# R220X.net
KiCad netlist of a schematic drawn in EAGLE
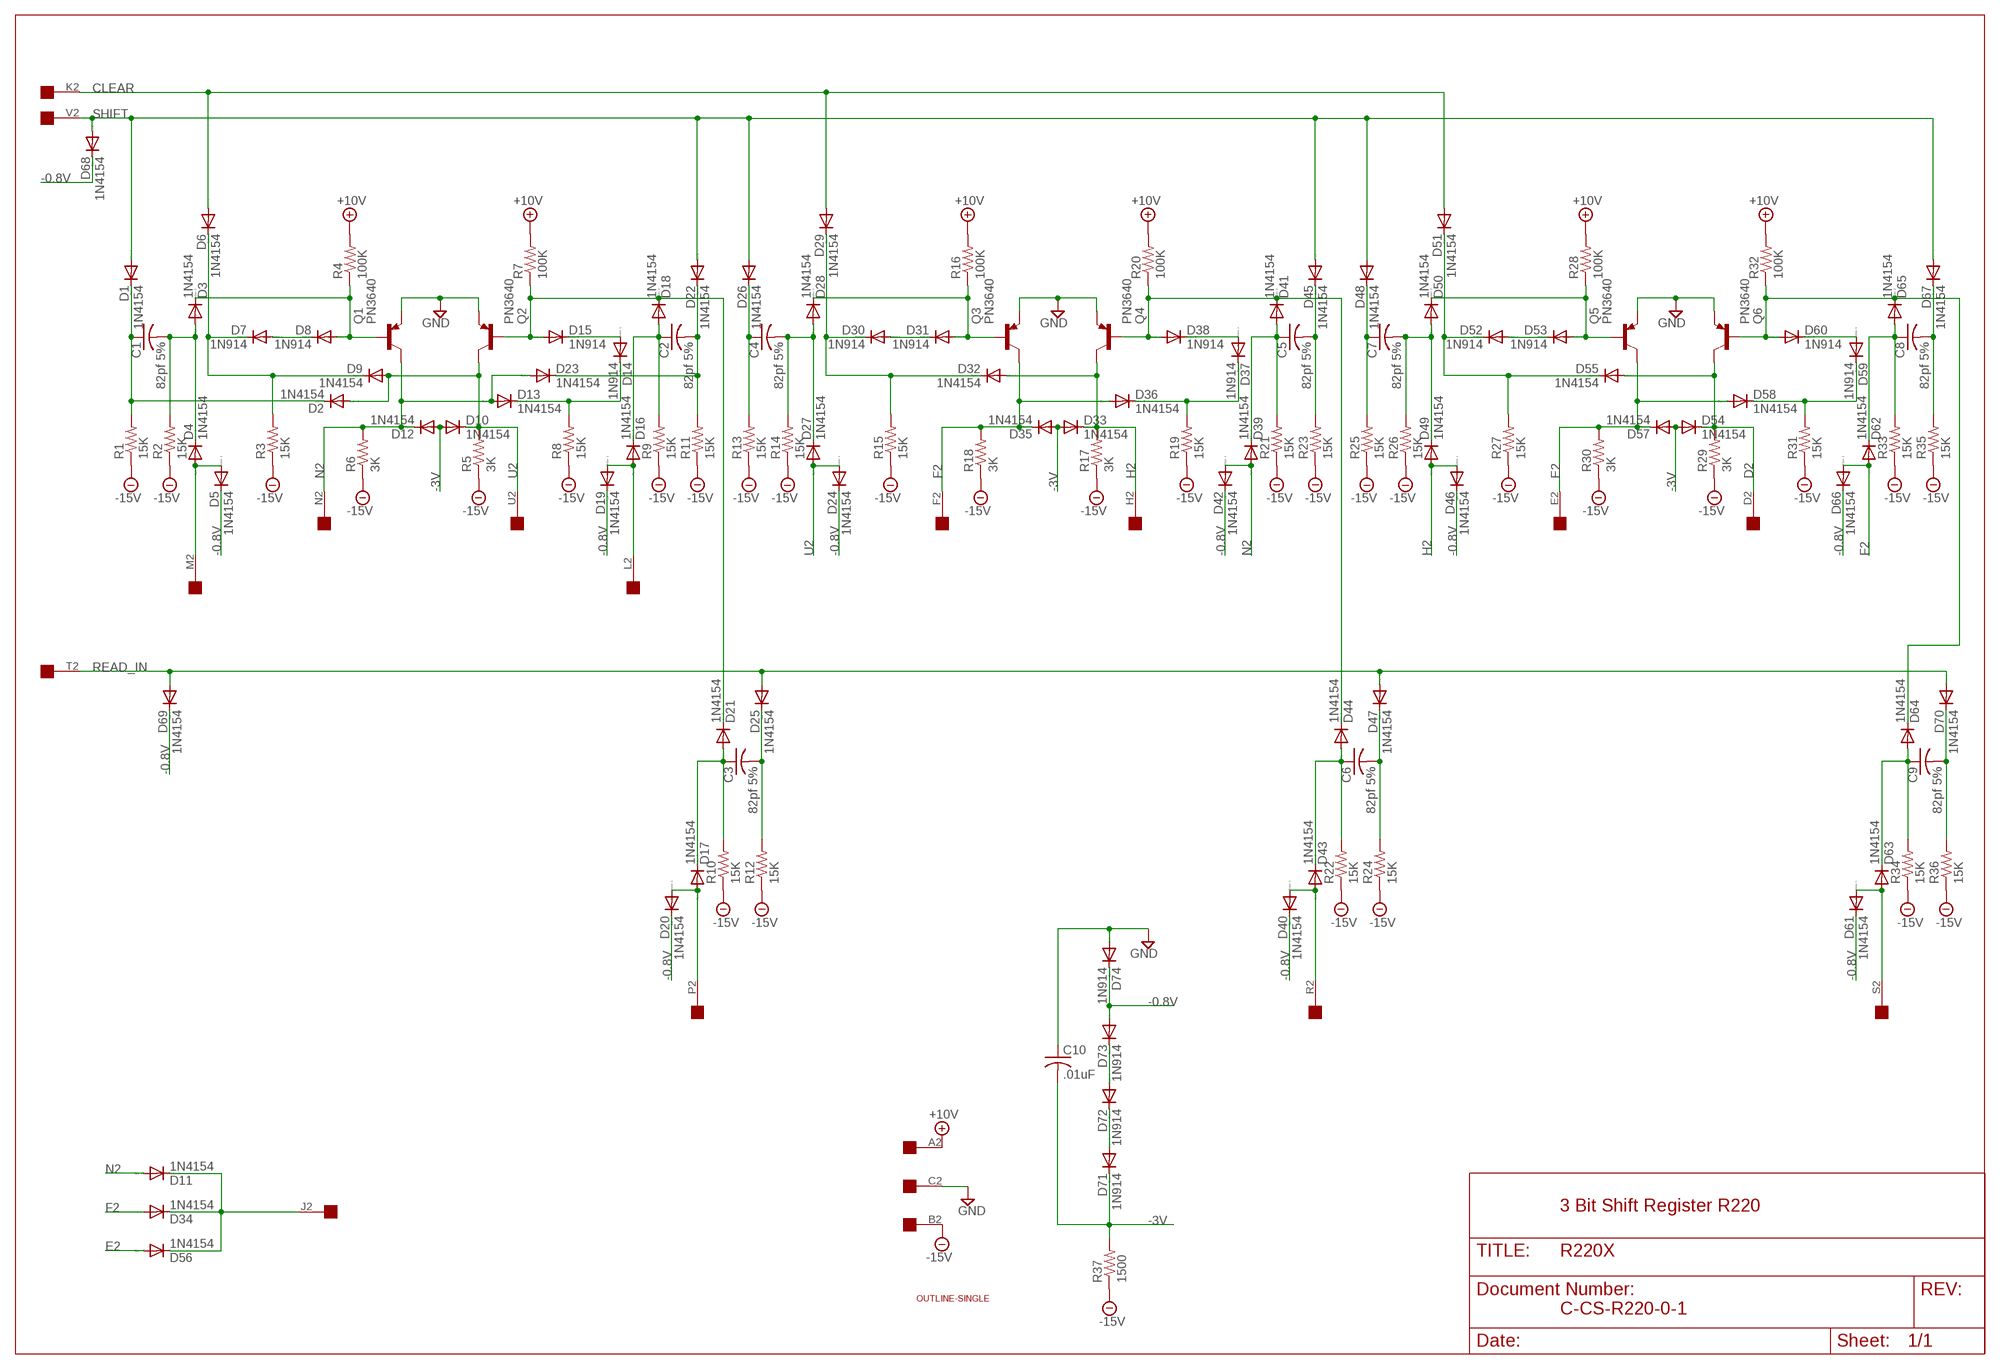
[diagram p0: schematic, sheet 1]

(export (version "E")
  (design (tool "Eeschema 10.0.6"))
  (components
    (comp (ref "C1")
      (value "82pf 5%")
      (footprint "eagle-import:C050-025X075")
      (libsource (lib "eagle-import") (part "C-US050-025X075"))
    )
    (comp (ref "C2")
      (value "82pf 5%")
      (footprint "eagle-import:C050-025X075")
      (libsource (lib "eagle-import") (part "C-US050-025X075"))
    )
    (comp (ref "C3")
      (value "82pf 5%")
      (footprint "eagle-import:C050-025X075")
      (libsource (lib "eagle-import") (part "C-US050-025X075"))
    )
    (comp (ref "C4")
      (value "82pf 5%")
      (footprint "eagle-import:C050-025X075")
      (libsource (lib "eagle-import") (part "C-US050-025X075"))
    )
    (comp (ref "C5")
      (value "82pf 5%")
      (footprint "eagle-import:C050-025X075")
      (libsource (lib "eagle-import") (part "C-US050-025X075"))
    )
    (comp (ref "C6")
      (value "82pf 5%")
      (footprint "eagle-import:C050-025X075")
      (libsource (lib "eagle-import") (part "C-US050-025X075"))
    )
    (comp (ref "C7")
      (value "82pf 5%")
      (footprint "eagle-import:C050-025X075")
      (libsource (lib "eagle-import") (part "C-US050-025X075"))
    )
    (comp (ref "C8")
      (value "82pf 5%")
      (footprint "eagle-import:C050-025X075")
      (libsource (lib "eagle-import") (part "C-US050-025X075"))
    )
    (comp (ref "C9")
      (value "82pf 5%")
      (footprint "eagle-import:C050-025X075")
      (libsource (lib "eagle-import") (part "C-US050-025X075"))
    )
    (comp (ref "C10")
      (value ".01uF")
      (footprint "eagle-import:C050-025X075")
      (libsource (lib "eagle-import") (part "C-US050-025X075"))
    )
    (comp (ref "D1")
      (value "1N4154")
      (footprint "eagle-import:DO35-10")
      (libsource (lib "eagle-import") (part "1N4148DO35-10"))
    )
    (comp (ref "D2")
      (value "1N4154")
      (footprint "eagle-import:DO35-10")
      (libsource (lib "eagle-import") (part "1N4148DO35-10"))
    )
    (comp (ref "D3")
      (value "1N4154")
      (footprint "eagle-import:DO35-10")
      (libsource (lib "eagle-import") (part "1N4148DO35-10"))
    )
    (comp (ref "D4")
      (value "1N4154")
      (footprint "eagle-import:DO35-10")
      (libsource (lib "eagle-import") (part "1N4148DO35-10"))
    )
    (comp (ref "D5")
      (value "1N4154")
      (footprint "eagle-import:DO35-10")
      (libsource (lib "eagle-import") (part "1N4148DO35-10"))
    )
    (comp (ref "D6")
      (value "1N4154")
      (footprint "eagle-import:DO35-10")
      (libsource (lib "eagle-import") (part "1N4148DO35-10"))
    )
    (comp (ref "D7")
      (value "1N914")
      (footprint "eagle-import:DO35-10")
      (libsource (lib "eagle-import") (part "1N4148DO35-10"))
    )
    (comp (ref "D8")
      (value "1N914")
      (footprint "eagle-import:DO35-10")
      (libsource (lib "eagle-import") (part "1N4148DO35-10"))
    )
    (comp (ref "D9")
      (value "1N4154")
      (footprint "eagle-import:DO35-10")
      (libsource (lib "eagle-import") (part "1N4148DO35-10"))
    )
    (comp (ref "D10")
      (value "1N4154")
      (footprint "eagle-import:DO35-10")
      (libsource (lib "eagle-import") (part "1N4148DO35-10"))
    )
    (comp (ref "D11")
      (value "1N4154")
      (footprint "eagle-import:DO35-10")
      (libsource (lib "eagle-import") (part "1N4148DO35-10"))
    )
    (comp (ref "D12")
      (value "1N4154")
      (footprint "eagle-import:DO35-10")
      (libsource (lib "eagle-import") (part "1N4148DO35-10"))
    )
    (comp (ref "D13")
      (value "1N4154")
      (footprint "eagle-import:DO35-10")
      (libsource (lib "eagle-import") (part "1N4148DO35-10"))
    )
    (comp (ref "D14")
      (value "1N914")
      (footprint "eagle-import:DO35-10")
      (libsource (lib "eagle-import") (part "1N4148DO35-10"))
    )
    (comp (ref "D15")
      (value "1N914")
      (footprint "eagle-import:DO35-10")
      (libsource (lib "eagle-import") (part "1N4148DO35-10"))
    )
    (comp (ref "D16")
      (value "1N4154")
      (footprint "eagle-import:DO35-10")
      (libsource (lib "eagle-import") (part "1N4148DO35-10"))
    )
    (comp (ref "D17")
      (value "1N4154")
      (footprint "eagle-import:DO35-10")
      (libsource (lib "eagle-import") (part "1N4148DO35-10"))
    )
    (comp (ref "D18")
      (value "1N4154")
      (footprint "eagle-import:DO35-10")
      (libsource (lib "eagle-import") (part "1N4148DO35-10"))
    )
    (comp (ref "D19")
      (value "1N4154")
      (footprint "eagle-import:DO35-10")
      (libsource (lib "eagle-import") (part "1N4148DO35-10"))
    )
    (comp (ref "D20")
      (value "1N4154")
      (footprint "eagle-import:DO35-10")
      (libsource (lib "eagle-import") (part "1N4148DO35-10"))
    )
    (comp (ref "D21")
      (value "1N4154")
      (footprint "eagle-import:DO35-10")
      (libsource (lib "eagle-import") (part "1N4148DO35-10"))
    )
    (comp (ref "D22")
      (value "1N4154")
      (footprint "eagle-import:DO35-10")
      (libsource (lib "eagle-import") (part "1N4148DO35-10"))
    )
    (comp (ref "D23")
      (value "1N4154")
      (footprint "eagle-import:DO35-10")
      (libsource (lib "eagle-import") (part "1N4148DO35-10"))
    )
    (comp (ref "D24")
      (value "1N4154")
      (footprint "eagle-import:DO35-10")
      (libsource (lib "eagle-import") (part "1N4148DO35-10"))
    )
    (comp (ref "D25")
      (value "1N4154")
      (footprint "eagle-import:DO35-10")
      (libsource (lib "eagle-import") (part "1N4148DO35-10"))
    )
    (comp (ref "D26")
      (value "1N4154")
      (footprint "eagle-import:DO35-10")
      (libsource (lib "eagle-import") (part "1N4148DO35-10"))
    )
    (comp (ref "D27")
      (value "1N4154")
      (footprint "eagle-import:DO35-10")
      (libsource (lib "eagle-import") (part "1N4148DO35-10"))
    )
    (comp (ref "D28")
      (value "1N4154")
      (footprint "eagle-import:DO35-10")
      (libsource (lib "eagle-import") (part "1N4148DO35-10"))
    )
    (comp (ref "D29")
      (value "1N4154")
      (footprint "eagle-import:DO35-10")
      (libsource (lib "eagle-import") (part "1N4148DO35-10"))
    )
    (comp (ref "D30")
      (value "1N914")
      (footprint "eagle-import:DO35-10")
      (libsource (lib "eagle-import") (part "1N4148DO35-10"))
    )
    (comp (ref "D31")
      (value "1N914")
      (footprint "eagle-import:DO35-10")
      (libsource (lib "eagle-import") (part "1N4148DO35-10"))
    )
    (comp (ref "D32")
      (value "1N4154")
      (footprint "eagle-import:DO35-10")
      (libsource (lib "eagle-import") (part "1N4148DO35-10"))
    )
    (comp (ref "D33")
      (value "1N4154")
      (footprint "eagle-import:DO35-10")
      (libsource (lib "eagle-import") (part "1N4148DO35-10"))
    )
    (comp (ref "D34")
      (value "1N4154")
      (footprint "eagle-import:DO35-10")
      (libsource (lib "eagle-import") (part "1N4148DO35-10"))
    )
    (comp (ref "D35")
      (value "1N4154")
      (footprint "eagle-import:DO35-10")
      (libsource (lib "eagle-import") (part "1N4148DO35-10"))
    )
    (comp (ref "D36")
      (value "1N4154")
      (footprint "eagle-import:DO35-10")
      (libsource (lib "eagle-import") (part "1N4148DO35-10"))
    )
    (comp (ref "D37")
      (value "1N914")
      (footprint "eagle-import:DO35-10")
      (libsource (lib "eagle-import") (part "1N4148DO35-10"))
    )
    (comp (ref "D38")
      (value "1N914")
      (footprint "eagle-import:DO35-10")
      (libsource (lib "eagle-import") (part "1N4148DO35-10"))
    )
    (comp (ref "D39")
      (value "1N4154")
      (footprint "eagle-import:DO35-10")
      (libsource (lib "eagle-import") (part "1N4148DO35-10"))
    )
    (comp (ref "D40")
      (value "1N4154")
      (footprint "eagle-import:DO35-10")
      (libsource (lib "eagle-import") (part "1N4148DO35-10"))
    )
    (comp (ref "D41")
      (value "1N4154")
      (footprint "eagle-import:DO35-10")
      (libsource (lib "eagle-import") (part "1N4148DO35-10"))
    )
    (comp (ref "D42")
      (value "1N4154")
      (footprint "eagle-import:DO35-10")
      (libsource (lib "eagle-import") (part "1N4148DO35-10"))
    )
    (comp (ref "D43")
      (value "1N4154")
      (footprint "eagle-import:DO35-10")
      (libsource (lib "eagle-import") (part "1N4148DO35-10"))
    )
    (comp (ref "D44")
      (value "1N4154")
      (footprint "eagle-import:DO35-10")
      (libsource (lib "eagle-import") (part "1N4148DO35-10"))
    )
    (comp (ref "D45")
      (value "1N4154")
      (footprint "eagle-import:DO35-10")
      (libsource (lib "eagle-import") (part "1N4148DO35-10"))
    )
    (comp (ref "D46")
      (value "1N4154")
      (footprint "eagle-import:DO35-10")
      (libsource (lib "eagle-import") (part "1N4148DO35-10"))
    )
    (comp (ref "D47")
      (value "1N4154")
      (footprint "eagle-import:DO35-10")
      (libsource (lib "eagle-import") (part "1N4148DO35-10"))
    )
    (comp (ref "D48")
      (value "1N4154")
      (footprint "eagle-import:DO35-10")
      (libsource (lib "eagle-import") (part "1N4148DO35-10"))
    )
    (comp (ref "D49")
      (value "1N4154")
      (footprint "eagle-import:DO35-10")
      (libsource (lib "eagle-import") (part "1N4148DO35-10"))
    )
    (comp (ref "D50")
      (value "1N4154")
      (footprint "eagle-import:DO35-10")
      (libsource (lib "eagle-import") (part "1N4148DO35-10"))
    )
    (comp (ref "D51")
      (value "1N4154")
      (footprint "eagle-import:DO35-10")
      (libsource (lib "eagle-import") (part "1N4148DO35-10"))
    )
    (comp (ref "D52")
      (value "1N914")
      (footprint "eagle-import:DO35-10")
      (libsource (lib "eagle-import") (part "1N4148DO35-10"))
    )
    (comp (ref "D53")
      (value "1N914")
      (footprint "eagle-import:DO35-10")
      (libsource (lib "eagle-import") (part "1N4148DO35-10"))
    )
    (comp (ref "D54")
      (value "1N4154")
      (footprint "eagle-import:DO35-10")
      (libsource (lib "eagle-import") (part "1N4148DO35-10"))
    )
    (comp (ref "D55")
      (value "1N4154")
      (footprint "eagle-import:DO35-10")
      (libsource (lib "eagle-import") (part "1N4148DO35-10"))
    )
    (comp (ref "D56")
      (value "1N4154")
      (footprint "eagle-import:DO35-10")
      (libsource (lib "eagle-import") (part "1N4148DO35-10"))
    )
    (comp (ref "D57")
      (value "1N4154")
      (footprint "eagle-import:DO35-10")
      (libsource (lib "eagle-import") (part "1N4148DO35-10"))
    )
    (comp (ref "D58")
      (value "1N4154")
      (footprint "eagle-import:DO35-10")
      (libsource (lib "eagle-import") (part "1N4148DO35-10"))
    )
    (comp (ref "D59")
      (value "1N914")
      (footprint "eagle-import:DO35-10")
      (libsource (lib "eagle-import") (part "1N4148DO35-10"))
    )
    (comp (ref "D60")
      (value "1N914")
      (footprint "eagle-import:DO35-10")
      (libsource (lib "eagle-import") (part "1N4148DO35-10"))
    )
    (comp (ref "D61")
      (value "1N4154")
      (footprint "eagle-import:DO35-10")
      (libsource (lib "eagle-import") (part "1N4148DO35-10"))
    )
    (comp (ref "D62")
      (value "1N4154")
      (footprint "eagle-import:DO35-10")
      (libsource (lib "eagle-import") (part "1N4148DO35-10"))
    )
    (comp (ref "D63")
      (value "1N4154")
      (footprint "eagle-import:DO35-10")
      (libsource (lib "eagle-import") (part "1N4148DO35-10"))
    )
    (comp (ref "D64")
      (value "1N4154")
      (footprint "eagle-import:DO35-10")
      (libsource (lib "eagle-import") (part "1N4148DO35-10"))
    )
    (comp (ref "D65")
      (value "1N4154")
      (footprint "eagle-import:DO35-10")
      (libsource (lib "eagle-import") (part "1N4148DO35-10"))
    )
    (comp (ref "D66")
      (value "1N4154")
      (footprint "eagle-import:DO35-10")
      (libsource (lib "eagle-import") (part "1N4148DO35-10"))
    )
    (comp (ref "D67")
      (value "1N4154")
      (footprint "eagle-import:DO35-10")
      (libsource (lib "eagle-import") (part "1N4148DO35-10"))
    )
    (comp (ref "D68")
      (value "1N4154")
      (footprint "eagle-import:DO35-10")
      (libsource (lib "eagle-import") (part "1N4148DO35-10"))
    )
    (comp (ref "D69")
      (value "1N4154")
      (footprint "eagle-import:DO35-10")
      (libsource (lib "eagle-import") (part "1N4148DO35-10"))
    )
    (comp (ref "D70")
      (value "1N4154")
      (footprint "eagle-import:DO35-10")
      (libsource (lib "eagle-import") (part "1N4148DO35-10"))
    )
    (comp (ref "D71")
      (value "1N914")
      (footprint "eagle-import:DO35-10")
      (libsource (lib "eagle-import") (part "1N4148DO35-10"))
    )
    (comp (ref "D72")
      (value "1N914")
      (footprint "eagle-import:DO35-10")
      (libsource (lib "eagle-import") (part "1N4148DO35-10"))
    )
    (comp (ref "D73")
      (value "1N914")
      (footprint "eagle-import:DO35-10")
      (libsource (lib "eagle-import") (part "1N4148DO35-10"))
    )
    (comp (ref "D74")
      (value "1N914")
      (footprint "eagle-import:DO35-10")
      (libsource (lib "eagle-import") (part "1N4148DO35-10"))
    )
    (comp (ref "Q1")
      (value "PN3640")
      (footprint "eagle-import:TO39")
      (libsource (lib "eagle-import") (part "2N3637"))
    )
    (comp (ref "Q2")
      (value "PN3640")
      (footprint "eagle-import:TO39")
      (libsource (lib "eagle-import") (part "2N3637"))
    )
    (comp (ref "Q3")
      (value "PN3640")
      (footprint "eagle-import:TO39")
      (libsource (lib "eagle-import") (part "2N3637"))
    )
    (comp (ref "Q4")
      (value "PN3640")
      (footprint "eagle-import:TO39")
      (libsource (lib "eagle-import") (part "2N3637"))
    )
    (comp (ref "Q5")
      (value "PN3640")
      (footprint "eagle-import:TO39")
      (libsource (lib "eagle-import") (part "2N3637"))
    )
    (comp (ref "Q6")
      (value "PN3640")
      (footprint "eagle-import:TO39")
      (libsource (lib "eagle-import") (part "2N3637"))
    )
    (comp (ref "R1")
      (value "15K")
      (footprint "eagle-import:0207_10")
      (libsource (lib "eagle-import") (part "R-US_0207/10"))
    )
    (comp (ref "R2")
      (value "15K")
      (footprint "eagle-import:0207_10")
      (libsource (lib "eagle-import") (part "R-US_0207/10"))
    )
    (comp (ref "R3")
      (value "15K")
      (footprint "eagle-import:0207_10")
      (libsource (lib "eagle-import") (part "R-US_0207/10"))
    )
    (comp (ref "R4")
      (value "100K")
      (footprint "eagle-import:0207_10")
      (libsource (lib "eagle-import") (part "R-US_0207/10"))
    )
    (comp (ref "R5")
      (value "3K")
      (footprint "eagle-import:0207_10")
      (libsource (lib "eagle-import") (part "R-US_0207/10"))
    )
    (comp (ref "R6")
      (value "3K")
      (footprint "eagle-import:0207_10")
      (libsource (lib "eagle-import") (part "R-US_0207/10"))
    )
    (comp (ref "R7")
      (value "100K")
      (footprint "eagle-import:0207_10")
      (libsource (lib "eagle-import") (part "R-US_0207/10"))
    )
    (comp (ref "R8")
      (value "15K")
      (footprint "eagle-import:0207_10")
      (libsource (lib "eagle-import") (part "R-US_0207/10"))
    )
    (comp (ref "R9")
      (value "15K")
      (footprint "eagle-import:0207_10")
      (libsource (lib "eagle-import") (part "R-US_0207/10"))
    )
    (comp (ref "R10")
      (value "15K")
      (footprint "eagle-import:0207_10")
      (libsource (lib "eagle-import") (part "R-US_0207/10"))
    )
    (comp (ref "R11")
      (value "15K")
      (footprint "eagle-import:0207_10")
      (libsource (lib "eagle-import") (part "R-US_0207/10"))
    )
    (comp (ref "R12")
      (value "15K")
      (footprint "eagle-import:0207_10")
      (libsource (lib "eagle-import") (part "R-US_0207/10"))
    )
    (comp (ref "R13")
      (value "15K")
      (footprint "eagle-import:0207_10")
      (libsource (lib "eagle-import") (part "R-US_0207/10"))
    )
    (comp (ref "R14")
      (value "15K")
      (footprint "eagle-import:0207_10")
      (libsource (lib "eagle-import") (part "R-US_0207/10"))
    )
    (comp (ref "R15")
      (value "15K")
      (footprint "eagle-import:0207_10")
      (libsource (lib "eagle-import") (part "R-US_0207/10"))
    )
    (comp (ref "R16")
      (value "100K")
      (footprint "eagle-import:0207_10")
      (libsource (lib "eagle-import") (part "R-US_0207/10"))
    )
    (comp (ref "R17")
      (value "3K")
      (footprint "eagle-import:0207_10")
      (libsource (lib "eagle-import") (part "R-US_0207/10"))
    )
    (comp (ref "R18")
      (value "3K")
      (footprint "eagle-import:0207_10")
      (libsource (lib "eagle-import") (part "R-US_0207/10"))
    )
    (comp (ref "R19")
      (value "15K")
      (footprint "eagle-import:0207_10")
      (libsource (lib "eagle-import") (part "R-US_0207/10"))
    )
    (comp (ref "R20")
      (value "100K")
      (footprint "eagle-import:0207_10")
      (libsource (lib "eagle-import") (part "R-US_0207/10"))
    )
    (comp (ref "R21")
      (value "15K")
      (footprint "eagle-import:0207_10")
      (libsource (lib "eagle-import") (part "R-US_0207/10"))
    )
    (comp (ref "R22")
      (value "15K")
      (footprint "eagle-import:0207_10")
      (libsource (lib "eagle-import") (part "R-US_0207/10"))
    )
    (comp (ref "R23")
      (value "15K")
      (footprint "eagle-import:0207_10")
      (libsource (lib "eagle-import") (part "R-US_0207/10"))
    )
    (comp (ref "R24")
      (value "15K")
      (footprint "eagle-import:0207_10")
      (libsource (lib "eagle-import") (part "R-US_0207/10"))
    )
    (comp (ref "R25")
      (value "15K")
      (footprint "eagle-import:0207_10")
      (libsource (lib "eagle-import") (part "R-US_0207/10"))
    )
    (comp (ref "R26")
      (value "15K")
      (footprint "eagle-import:0207_10")
      (libsource (lib "eagle-import") (part "R-US_0207/10"))
    )
    (comp (ref "R27")
      (value "15K")
      (footprint "eagle-import:0207_10")
      (libsource (lib "eagle-import") (part "R-US_0207/10"))
    )
    (comp (ref "R28")
      (value "100K")
      (footprint "eagle-import:0207_10")
      (libsource (lib "eagle-import") (part "R-US_0207/10"))
    )
    (comp (ref "R29")
      (value "3K")
      (footprint "eagle-import:0207_10")
      (libsource (lib "eagle-import") (part "R-US_0207/10"))
    )
    (comp (ref "R30")
      (value "3K")
      (footprint "eagle-import:0207_10")
      (libsource (lib "eagle-import") (part "R-US_0207/10"))
    )
    (comp (ref "R31")
      (value "15K")
      (footprint "eagle-import:0207_10")
      (libsource (lib "eagle-import") (part "R-US_0207/10"))
    )
    (comp (ref "R32")
      (value "100K")
      (footprint "eagle-import:0207_10")
      (libsource (lib "eagle-import") (part "R-US_0207/10"))
    )
    (comp (ref "R33")
      (value "15K")
      (footprint "eagle-import:0207_10")
      (libsource (lib "eagle-import") (part "R-US_0207/10"))
    )
    (comp (ref "R34")
      (value "15K")
      (footprint "eagle-import:0207_10")
      (libsource (lib "eagle-import") (part "R-US_0207/10"))
    )
    (comp (ref "R35")
      (value "15K")
      (footprint "eagle-import:0207_10")
      (libsource (lib "eagle-import") (part "R-US_0207/10"))
    )
    (comp (ref "R36")
      (value "15K")
      (footprint "eagle-import:0207_10")
      (libsource (lib "eagle-import") (part "R-US_0207/10"))
    )
    (comp (ref "R37")
      (value "1500")
      (footprint "eagle-import:0207_10")
      (libsource (lib "eagle-import") (part "R-US_0207/10"))
    )
    (comp (ref "U$1")
      (value "OUTLINE-SINGLE")
      (footprint "eagle-import:SINGLE")
      (libsource (lib "eagle-import") (part "OUTLINE-SINGLE"))
    )
    (comp (ref "U$2")
      (value "EDGE-1")
      (footprint "eagle-import:EDGE-CON1")
      (libsource (lib "eagle-import") (part "EDGE-1"))
    )
  )
  (nets
    (net (code "1") (name "+10V") (class "Default")
      (node (ref "R16") (pin "2") (pinfunction "2_2") (pintype "passive"))
      (node (ref "R20") (pin "2") (pinfunction "2_2") (pintype "passive"))
      (node (ref "R28") (pin "2") (pinfunction "2_2") (pintype "passive"))
      (node (ref "R32") (pin "2") (pinfunction "2_2") (pintype "passive"))
      (node (ref "R4") (pin "2") (pinfunction "2_2") (pintype "passive"))
      (node (ref "R7") (pin "2") (pinfunction "2_2") (pintype "passive"))
      (node (ref "U$2") (pin "A2") (pinfunction "1_A2") (pintype "bidirectional"))
    )
    (net (code "2") (name "-15V") (class "Default")
      (node (ref "R1") (pin "1") (pinfunction "1_1") (pintype "passive"))
      (node (ref "R10") (pin "1") (pinfunction "1_1") (pintype "passive"))
      (node (ref "R11") (pin "1") (pinfunction "1_1") (pintype "passive"))
      (node (ref "R12") (pin "1") (pinfunction "1_1") (pintype "passive"))
      (node (ref "R13") (pin "1") (pinfunction "1_1") (pintype "passive"))
      (node (ref "R14") (pin "1") (pinfunction "1_1") (pintype "passive"))
      (node (ref "R15") (pin "1") (pinfunction "1_1") (pintype "passive"))
      (node (ref "R17") (pin "1") (pinfunction "1_1") (pintype "passive"))
      (node (ref "R18") (pin "1") (pinfunction "1_1") (pintype "passive"))
      (node (ref "R19") (pin "1") (pinfunction "1_1") (pintype "passive"))
      (node (ref "R2") (pin "1") (pinfunction "1_1") (pintype "passive"))
      (node (ref "R21") (pin "1") (pinfunction "1_1") (pintype "passive"))
      (node (ref "R22") (pin "1") (pinfunction "1_1") (pintype "passive"))
      (node (ref "R23") (pin "1") (pinfunction "1_1") (pintype "passive"))
      (node (ref "R24") (pin "1") (pinfunction "1_1") (pintype "passive"))
      (node (ref "R25") (pin "1") (pinfunction "1_1") (pintype "passive"))
      (node (ref "R26") (pin "1") (pinfunction "1_1") (pintype "passive"))
      (node (ref "R27") (pin "1") (pinfunction "1_1") (pintype "passive"))
      (node (ref "R29") (pin "1") (pinfunction "1_1") (pintype "passive"))
      (node (ref "R3") (pin "1") (pinfunction "1_1") (pintype "passive"))
      (node (ref "R30") (pin "1") (pinfunction "1_1") (pintype "passive"))
      (node (ref "R31") (pin "1") (pinfunction "1_1") (pintype "passive"))
      (node (ref "R33") (pin "1") (pinfunction "1_1") (pintype "passive"))
      (node (ref "R34") (pin "1") (pinfunction "1_1") (pintype "passive"))
      (node (ref "R35") (pin "1") (pinfunction "1_1") (pintype "passive"))
      (node (ref "R36") (pin "1") (pinfunction "1_1") (pintype "passive"))
      (node (ref "R37") (pin "1") (pinfunction "1_1") (pintype "passive"))
      (node (ref "R5") (pin "1") (pinfunction "1_1") (pintype "passive"))
      (node (ref "R6") (pin "1") (pinfunction "1_1") (pintype "passive"))
      (node (ref "R8") (pin "1") (pinfunction "1_1") (pintype "passive"))
      (node (ref "R9") (pin "1") (pinfunction "1_1") (pintype "passive"))
      (node (ref "U$2") (pin "B2") (pinfunction "1_B2") (pintype "bidirectional"))
    )
    (net (code "3") (name "/-0.8V") (class "Default")
      (node (ref "D19") (pin "C") (pinfunction "C_C") (pintype "passive"))
      (node (ref "D20") (pin "C") (pinfunction "C_C") (pintype "passive"))
      (node (ref "D24") (pin "C") (pinfunction "C_C") (pintype "passive"))
      (node (ref "D40") (pin "C") (pinfunction "C_C") (pintype "passive"))
      (node (ref "D42") (pin "C") (pinfunction "C_C") (pintype "passive"))
      (node (ref "D46") (pin "C") (pinfunction "C_C") (pintype "passive"))
      (node (ref "D5") (pin "C") (pinfunction "C_C") (pintype "passive"))
      (node (ref "D61") (pin "C") (pinfunction "C_C") (pintype "passive"))
      (node (ref "D66") (pin "C") (pinfunction "C_C") (pintype "passive"))
      (node (ref "D68") (pin "C") (pinfunction "C_C") (pintype "passive"))
      (node (ref "D69") (pin "C") (pinfunction "C_C") (pintype "passive"))
      (node (ref "D73") (pin "A") (pinfunction "A_A") (pintype "passive"))
      (node (ref "D74") (pin "C") (pinfunction "C_C") (pintype "passive"))
    )
    (net (code "4") (name "/-3V") (class "Default")
      (node (ref "C10") (pin "2") (pinfunction "2_2") (pintype "passive"))
      (node (ref "D10") (pin "A") (pinfunction "A_A") (pintype "passive"))
      (node (ref "D12") (pin "A") (pinfunction "A_A") (pintype "passive"))
      (node (ref "D33") (pin "A") (pinfunction "A_A") (pintype "passive"))
      (node (ref "D35") (pin "A") (pinfunction "A_A") (pintype "passive"))
      (node (ref "D54") (pin "A") (pinfunction "A_A") (pintype "passive"))
      (node (ref "D57") (pin "A") (pinfunction "A_A") (pintype "passive"))
      (node (ref "D71") (pin "C") (pinfunction "C_C") (pintype "passive"))
      (node (ref "R37") (pin "2") (pinfunction "2_2") (pintype "passive"))
    )
    (net (code "5") (name "/CLEAR") (class "Default")
      (node (ref "D29") (pin "A") (pinfunction "A_A") (pintype "passive"))
      (node (ref "D51") (pin "A") (pinfunction "A_A") (pintype "passive"))
      (node (ref "D6") (pin "A") (pinfunction "A_A") (pintype "passive"))
      (node (ref "U$2") (pin "K2") (pinfunction "1_K2") (pintype "bidirectional"))
    )
    (net (code "6") (name "/D2") (class "Default")
      (node (ref "D54") (pin "C") (pinfunction "C_C") (pintype "passive"))
      (node (ref "D55") (pin "A") (pinfunction "A_A") (pintype "passive"))
      (node (ref "Q6") (pin "3") (pinfunction "C_3") (pintype "passive"))
      (node (ref "R29") (pin "2") (pinfunction "2_2") (pintype "passive"))
      (node (ref "U$2") (pin "D2") (pinfunction "1_D2") (pintype "bidirectional"))
    )
    (net (code "7") (name "/E2") (class "Default")
      (node (ref "D56") (pin "A") (pinfunction "A_A") (pintype "passive"))
      (node (ref "D57") (pin "C") (pinfunction "C_C") (pintype "passive"))
      (node (ref "D58") (pin "A") (pinfunction "A_A") (pintype "passive"))
      (node (ref "Q5") (pin "3") (pinfunction "C_3") (pintype "passive"))
      (node (ref "R30") (pin "2") (pinfunction "2_2") (pintype "passive"))
      (node (ref "U$2") (pin "E2") (pinfunction "1_E2") (pintype "bidirectional"))
    )
    (net (code "8") (name "/F2") (class "Default")
      (node (ref "D34") (pin "A") (pinfunction "A_A") (pintype "passive"))
      (node (ref "D35") (pin "C") (pinfunction "C_C") (pintype "passive"))
      (node (ref "D36") (pin "A") (pinfunction "A_A") (pintype "passive"))
      (node (ref "D62") (pin "A") (pinfunction "A_A") (pintype "passive"))
      (node (ref "D66") (pin "A") (pinfunction "A_A") (pintype "passive"))
      (node (ref "Q3") (pin "3") (pinfunction "C_3") (pintype "passive"))
      (node (ref "R18") (pin "2") (pinfunction "2_2") (pintype "passive"))
      (node (ref "U$2") (pin "F2") (pinfunction "1_F2") (pintype "bidirectional"))
    )
    (net (code "9") (name "/H2") (class "Default")
      (node (ref "D32") (pin "A") (pinfunction "A_A") (pintype "passive"))
      (node (ref "D33") (pin "C") (pinfunction "C_C") (pintype "passive"))
      (node (ref "D46") (pin "A") (pinfunction "A_A") (pintype "passive"))
      (node (ref "D49") (pin "A") (pinfunction "A_A") (pintype "passive"))
      (node (ref "Q4") (pin "3") (pinfunction "C_3") (pintype "passive"))
      (node (ref "R17") (pin "2") (pinfunction "2_2") (pintype "passive"))
      (node (ref "U$2") (pin "H2") (pinfunction "1_H2") (pintype "bidirectional"))
    )
    (net (code "10") (name "/N2") (class "Default")
      (node (ref "D11") (pin "A") (pinfunction "A_A") (pintype "passive"))
      (node (ref "D12") (pin "C") (pinfunction "C_C") (pintype "passive"))
      (node (ref "D13") (pin "A") (pinfunction "A_A") (pintype "passive"))
      (node (ref "D23") (pin "A") (pinfunction "A_A") (pintype "passive"))
      (node (ref "D39") (pin "A") (pinfunction "A_A") (pintype "passive"))
      (node (ref "D42") (pin "A") (pinfunction "A_A") (pintype "passive"))
      (node (ref "Q1") (pin "3") (pinfunction "C_3") (pintype "passive"))
      (node (ref "R6") (pin "2") (pinfunction "2_2") (pintype "passive"))
      (node (ref "U$2") (pin "N2") (pinfunction "1_N2") (pintype "bidirectional"))
    )
    (net (code "11") (name "/READ_IN") (class "Default")
      (node (ref "D25") (pin "A") (pinfunction "A_A") (pintype "passive"))
      (node (ref "D47") (pin "A") (pinfunction "A_A") (pintype "passive"))
      (node (ref "D69") (pin "A") (pinfunction "A_A") (pintype "passive"))
      (node (ref "D70") (pin "A") (pinfunction "A_A") (pintype "passive"))
      (node (ref "U$2") (pin "T2") (pinfunction "1_T2") (pintype "bidirectional"))
    )
    (net (code "12") (name "/SHIFT") (class "Default")
      (node (ref "D1") (pin "A") (pinfunction "A_A") (pintype "passive"))
      (node (ref "D22") (pin "A") (pinfunction "A_A") (pintype "passive"))
      (node (ref "D26") (pin "A") (pinfunction "A_A") (pintype "passive"))
      (node (ref "D45") (pin "A") (pinfunction "A_A") (pintype "passive"))
      (node (ref "D48") (pin "A") (pinfunction "A_A") (pintype "passive"))
      (node (ref "D67") (pin "A") (pinfunction "A_A") (pintype "passive"))
      (node (ref "D68") (pin "A") (pinfunction "A_A") (pintype "passive"))
      (node (ref "U$2") (pin "V2") (pinfunction "1_V2") (pintype "bidirectional"))
    )
    (net (code "13") (name "/U2") (class "Default")
      (node (ref "D10") (pin "C") (pinfunction "C_C") (pintype "passive"))
      (node (ref "D2") (pin "A") (pinfunction "A_A") (pintype "passive"))
      (node (ref "D24") (pin "A") (pinfunction "A_A") (pintype "passive"))
      (node (ref "D27") (pin "A") (pinfunction "A_A") (pintype "passive"))
      (node (ref "D9") (pin "A") (pinfunction "A_A") (pintype "passive"))
      (node (ref "Q2") (pin "3") (pinfunction "C_3") (pintype "passive"))
      (node (ref "R5") (pin "2") (pinfunction "2_2") (pintype "passive"))
      (node (ref "U$2") (pin "U2") (pinfunction "1_U2") (pintype "bidirectional"))
    )
    (net (code "14") (name "GND") (class "Default")
      (node (ref "C10") (pin "1") (pinfunction "1_1") (pintype "passive"))
      (node (ref "D74") (pin "A") (pinfunction "A_A") (pintype "passive"))
      (node (ref "Q1") (pin "1") (pinfunction "E_1") (pintype "passive"))
      (node (ref "Q2") (pin "1") (pinfunction "E_1") (pintype "passive"))
      (node (ref "Q3") (pin "1") (pinfunction "E_1") (pintype "passive"))
      (node (ref "Q4") (pin "1") (pinfunction "E_1") (pintype "passive"))
      (node (ref "Q5") (pin "1") (pinfunction "E_1") (pintype "passive"))
      (node (ref "Q6") (pin "1") (pinfunction "E_1") (pintype "passive"))
      (node (ref "U$2") (pin "C2") (pinfunction "1_C2") (pintype "bidirectional"))
    )
    (net (code "15") (name "Net-(C1-Pad1)") (class "Default")
      (node (ref "C1") (pin "1") (pinfunction "1_1") (pintype "passive"))
      (node (ref "D1") (pin "C") (pinfunction "C_C") (pintype "passive"))
      (node (ref "D2") (pin "C") (pinfunction "C_C") (pintype "passive"))
      (node (ref "R1") (pin "2") (pinfunction "2_2") (pintype "passive"))
    )
    (net (code "16") (name "Net-(C1-Pad2)") (class "Default")
      (node (ref "C1") (pin "2") (pinfunction "2_2") (pintype "passive"))
      (node (ref "D3") (pin "A") (pinfunction "A_A") (pintype "passive"))
      (node (ref "D4") (pin "C") (pinfunction "C_C") (pintype "passive"))
      (node (ref "R2") (pin "2") (pinfunction "2_2") (pintype "passive"))
    )
    (net (code "17") (name "Net-(C2-Pad1)") (class "Default")
      (node (ref "C2") (pin "1") (pinfunction "1_1") (pintype "passive"))
      (node (ref "D16") (pin "C") (pinfunction "C_C") (pintype "passive"))
      (node (ref "D18") (pin "A") (pinfunction "A_A") (pintype "passive"))
      (node (ref "R9") (pin "2") (pinfunction "2_2") (pintype "passive"))
    )
    (net (code "18") (name "Net-(C2-Pad2)") (class "Default")
      (node (ref "C2") (pin "2") (pinfunction "2_2") (pintype "passive"))
      (node (ref "D22") (pin "C") (pinfunction "C_C") (pintype "passive"))
      (node (ref "D23") (pin "C") (pinfunction "C_C") (pintype "passive"))
      (node (ref "R11") (pin "2") (pinfunction "2_2") (pintype "passive"))
    )
    (net (code "19") (name "Net-(C3-Pad1)") (class "Default")
      (node (ref "C3") (pin "1") (pinfunction "1_1") (pintype "passive"))
      (node (ref "D17") (pin "C") (pinfunction "C_C") (pintype "passive"))
      (node (ref "D21") (pin "A") (pinfunction "A_A") (pintype "passive"))
      (node (ref "R10") (pin "2") (pinfunction "2_2") (pintype "passive"))
    )
    (net (code "20") (name "Net-(C3-Pad2)") (class "Default")
      (node (ref "C3") (pin "2") (pinfunction "2_2") (pintype "passive"))
      (node (ref "D25") (pin "C") (pinfunction "C_C") (pintype "passive"))
      (node (ref "R12") (pin "2") (pinfunction "2_2") (pintype "passive"))
    )
    (net (code "21") (name "Net-(C4-Pad1)") (class "Default")
      (node (ref "C4") (pin "1") (pinfunction "1_1") (pintype "passive"))
      (node (ref "D26") (pin "C") (pinfunction "C_C") (pintype "passive"))
      (node (ref "R13") (pin "2") (pinfunction "2_2") (pintype "passive"))
    )
    (net (code "22") (name "Net-(C4-Pad2)") (class "Default")
      (node (ref "C4") (pin "2") (pinfunction "2_2") (pintype "passive"))
      (node (ref "D27") (pin "C") (pinfunction "C_C") (pintype "passive"))
      (node (ref "D28") (pin "A") (pinfunction "A_A") (pintype "passive"))
      (node (ref "R14") (pin "2") (pinfunction "2_2") (pintype "passive"))
    )
    (net (code "23") (name "Net-(C5-Pad1)") (class "Default")
      (node (ref "C5") (pin "1") (pinfunction "1_1") (pintype "passive"))
      (node (ref "D39") (pin "C") (pinfunction "C_C") (pintype "passive"))
      (node (ref "D41") (pin "A") (pinfunction "A_A") (pintype "passive"))
      (node (ref "R21") (pin "2") (pinfunction "2_2") (pintype "passive"))
    )
    (net (code "24") (name "Net-(C5-Pad2)") (class "Default")
      (node (ref "C5") (pin "2") (pinfunction "2_2") (pintype "passive"))
      (node (ref "D45") (pin "C") (pinfunction "C_C") (pintype "passive"))
      (node (ref "R23") (pin "2") (pinfunction "2_2") (pintype "passive"))
    )
    (net (code "25") (name "Net-(C6-Pad1)") (class "Default")
      (node (ref "C6") (pin "1") (pinfunction "1_1") (pintype "passive"))
      (node (ref "D43") (pin "C") (pinfunction "C_C") (pintype "passive"))
      (node (ref "D44") (pin "A") (pinfunction "A_A") (pintype "passive"))
      (node (ref "R22") (pin "2") (pinfunction "2_2") (pintype "passive"))
    )
    (net (code "26") (name "Net-(C6-Pad2)") (class "Default")
      (node (ref "C6") (pin "2") (pinfunction "2_2") (pintype "passive"))
      (node (ref "D47") (pin "C") (pinfunction "C_C") (pintype "passive"))
      (node (ref "R24") (pin "2") (pinfunction "2_2") (pintype "passive"))
    )
    (net (code "27") (name "Net-(C7-Pad1)") (class "Default")
      (node (ref "C7") (pin "1") (pinfunction "1_1") (pintype "passive"))
      (node (ref "D48") (pin "C") (pinfunction "C_C") (pintype "passive"))
      (node (ref "R25") (pin "2") (pinfunction "2_2") (pintype "passive"))
    )
    (net (code "28") (name "Net-(C7-Pad2)") (class "Default")
      (node (ref "C7") (pin "2") (pinfunction "2_2") (pintype "passive"))
      (node (ref "D49") (pin "C") (pinfunction "C_C") (pintype "passive"))
      (node (ref "D50") (pin "A") (pinfunction "A_A") (pintype "passive"))
      (node (ref "R26") (pin "2") (pinfunction "2_2") (pintype "passive"))
    )
    (net (code "29") (name "Net-(C8-Pad1)") (class "Default")
      (node (ref "C8") (pin "1") (pinfunction "1_1") (pintype "passive"))
      (node (ref "D62") (pin "C") (pinfunction "C_C") (pintype "passive"))
      (node (ref "D65") (pin "A") (pinfunction "A_A") (pintype "passive"))
      (node (ref "R33") (pin "2") (pinfunction "2_2") (pintype "passive"))
    )
    (net (code "30") (name "Net-(C8-Pad2)") (class "Default")
      (node (ref "C8") (pin "2") (pinfunction "2_2") (pintype "passive"))
      (node (ref "D67") (pin "C") (pinfunction "C_C") (pintype "passive"))
      (node (ref "R35") (pin "2") (pinfunction "2_2") (pintype "passive"))
    )
    (net (code "31") (name "Net-(C9-Pad1)") (class "Default")
      (node (ref "C9") (pin "1") (pinfunction "1_1") (pintype "passive"))
      (node (ref "D63") (pin "C") (pinfunction "C_C") (pintype "passive"))
      (node (ref "D64") (pin "A") (pinfunction "A_A") (pintype "passive"))
      (node (ref "R34") (pin "2") (pinfunction "2_2") (pintype "passive"))
    )
    (net (code "32") (name "Net-(C9-Pad2)") (class "Default")
      (node (ref "C9") (pin "2") (pinfunction "2_2") (pintype "passive"))
      (node (ref "D70") (pin "C") (pinfunction "C_C") (pintype "passive"))
      (node (ref "R36") (pin "2") (pinfunction "2_2") (pintype "passive"))
    )
    (net (code "33") (name "Net-(D6-PadC)") (class "Default")
      (node (ref "D6") (pin "C") (pinfunction "C_C") (pintype "passive"))
      (node (ref "D7") (pin "C") (pinfunction "C_C") (pintype "passive"))
      (node (ref "D9") (pin "C") (pinfunction "C_C") (pintype "passive"))
      (node (ref "R3") (pin "2") (pinfunction "2_2") (pintype "passive"))
    )
    (net (code "34") (name "Net-(D7-PadA)") (class "Default")
      (node (ref "D7") (pin "A") (pinfunction "A_A") (pintype "passive"))
      (node (ref "D8") (pin "C") (pinfunction "C_C") (pintype "passive"))
    )
    (net (code "35") (name "Net-(D13-PadC)") (class "Default")
      (node (ref "D13") (pin "C") (pinfunction "C_C") (pintype "passive"))
      (node (ref "D14") (pin "C") (pinfunction "C_C") (pintype "passive"))
      (node (ref "R8") (pin "2") (pinfunction "2_2") (pintype "passive"))
    )
    (net (code "36") (name "Net-(D14-PadA)") (class "Default")
      (node (ref "D14") (pin "A") (pinfunction "A_A") (pintype "passive"))
      (node (ref "D15") (pin "C") (pinfunction "C_C") (pintype "passive"))
    )
    (net (code "37") (name "Net-(D29-PadC)") (class "Default")
      (node (ref "D29") (pin "C") (pinfunction "C_C") (pintype "passive"))
      (node (ref "D30") (pin "C") (pinfunction "C_C") (pintype "passive"))
      (node (ref "D32") (pin "C") (pinfunction "C_C") (pintype "passive"))
      (node (ref "R15") (pin "2") (pinfunction "2_2") (pintype "passive"))
    )
    (net (code "38") (name "Net-(D30-PadA)") (class "Default")
      (node (ref "D30") (pin "A") (pinfunction "A_A") (pintype "passive"))
      (node (ref "D31") (pin "C") (pinfunction "C_C") (pintype "passive"))
    )
    (net (code "39") (name "Net-(D36-PadC)") (class "Default")
      (node (ref "D36") (pin "C") (pinfunction "C_C") (pintype "passive"))
      (node (ref "D37") (pin "C") (pinfunction "C_C") (pintype "passive"))
      (node (ref "R19") (pin "2") (pinfunction "2_2") (pintype "passive"))
    )
    (net (code "40") (name "Net-(D37-PadA)") (class "Default")
      (node (ref "D37") (pin "A") (pinfunction "A_A") (pintype "passive"))
      (node (ref "D38") (pin "C") (pinfunction "C_C") (pintype "passive"))
    )
    (net (code "41") (name "Net-(D51-PadC)") (class "Default")
      (node (ref "D51") (pin "C") (pinfunction "C_C") (pintype "passive"))
      (node (ref "D52") (pin "C") (pinfunction "C_C") (pintype "passive"))
      (node (ref "D55") (pin "C") (pinfunction "C_C") (pintype "passive"))
      (node (ref "R27") (pin "2") (pinfunction "2_2") (pintype "passive"))
    )
    (net (code "42") (name "Net-(D52-PadA)") (class "Default")
      (node (ref "D52") (pin "A") (pinfunction "A_A") (pintype "passive"))
      (node (ref "D53") (pin "C") (pinfunction "C_C") (pintype "passive"))
    )
    (net (code "43") (name "Net-(D58-PadC)") (class "Default")
      (node (ref "D58") (pin "C") (pinfunction "C_C") (pintype "passive"))
      (node (ref "D59") (pin "C") (pinfunction "C_C") (pintype "passive"))
      (node (ref "R31") (pin "2") (pinfunction "2_2") (pintype "passive"))
    )
    (net (code "44") (name "Net-(D59-PadA)") (class "Default")
      (node (ref "D59") (pin "A") (pinfunction "A_A") (pintype "passive"))
      (node (ref "D60") (pin "C") (pinfunction "C_C") (pintype "passive"))
    )
    (net (code "45") (name "Net-(D71-PadA)") (class "Default")
      (node (ref "D71") (pin "A") (pinfunction "A_A") (pintype "passive"))
      (node (ref "D72") (pin "C") (pinfunction "C_C") (pintype "passive"))
    )
    (net (code "46") (name "Net-(D72-PadA)") (class "Default")
      (node (ref "D72") (pin "A") (pinfunction "A_A") (pintype "passive"))
      (node (ref "D73") (pin "C") (pinfunction "C_C") (pintype "passive"))
    )
    (net (code "47") (name "Net-(Q1-B)") (class "Default")
      (node (ref "D3") (pin "C") (pinfunction "C_C") (pintype "passive"))
      (node (ref "D8") (pin "A") (pinfunction "A_A") (pintype "passive"))
      (node (ref "Q1") (pin "2") (pinfunction "B_2") (pintype "passive"))
      (node (ref "R4") (pin "1") (pinfunction "1_1") (pintype "passive"))
    )
    (net (code "48") (name "Net-(Q2-B)") (class "Default")
      (node (ref "D15") (pin "A") (pinfunction "A_A") (pintype "passive"))
      (node (ref "D18") (pin "C") (pinfunction "C_C") (pintype "passive"))
      (node (ref "D21") (pin "C") (pinfunction "C_C") (pintype "passive"))
      (node (ref "Q2") (pin "2") (pinfunction "B_2") (pintype "passive"))
      (node (ref "R7") (pin "1") (pinfunction "1_1") (pintype "passive"))
    )
    (net (code "49") (name "Net-(Q3-B)") (class "Default")
      (node (ref "D28") (pin "C") (pinfunction "C_C") (pintype "passive"))
      (node (ref "D31") (pin "A") (pinfunction "A_A") (pintype "passive"))
      (node (ref "Q3") (pin "2") (pinfunction "B_2") (pintype "passive"))
      (node (ref "R16") (pin "1") (pinfunction "1_1") (pintype "passive"))
    )
    (net (code "50") (name "Net-(Q4-B)") (class "Default")
      (node (ref "D38") (pin "A") (pinfunction "A_A") (pintype "passive"))
      (node (ref "D41") (pin "C") (pinfunction "C_C") (pintype "passive"))
      (node (ref "D44") (pin "C") (pinfunction "C_C") (pintype "passive"))
      (node (ref "Q4") (pin "2") (pinfunction "B_2") (pintype "passive"))
      (node (ref "R20") (pin "1") (pinfunction "1_1") (pintype "passive"))
    )
    (net (code "51") (name "Net-(Q5-B)") (class "Default")
      (node (ref "D50") (pin "C") (pinfunction "C_C") (pintype "passive"))
      (node (ref "D53") (pin "A") (pinfunction "A_A") (pintype "passive"))
      (node (ref "Q5") (pin "2") (pinfunction "B_2") (pintype "passive"))
      (node (ref "R28") (pin "1") (pinfunction "1_1") (pintype "passive"))
    )
    (net (code "52") (name "Net-(Q6-B)") (class "Default")
      (node (ref "D60") (pin "A") (pinfunction "A_A") (pintype "passive"))
      (node (ref "D64") (pin "C") (pinfunction "C_C") (pintype "passive"))
      (node (ref "D65") (pin "C") (pinfunction "C_C") (pintype "passive"))
      (node (ref "Q6") (pin "2") (pinfunction "B_2") (pintype "passive"))
      (node (ref "R32") (pin "1") (pinfunction "1_1") (pintype "passive"))
    )
    (net (code "53") (name "Net-(U$2H-1)") (class "Default")
      (node (ref "D11") (pin "C") (pinfunction "C_C") (pintype "passive"))
      (node (ref "D34") (pin "C") (pinfunction "C_C") (pintype "passive"))
      (node (ref "D56") (pin "C") (pinfunction "C_C") (pintype "passive"))
      (node (ref "U$2") (pin "J2") (pinfunction "1_J2") (pintype "bidirectional"))
    )
    (net (code "54") (name "Net-(U$2J-1)") (class "Default")
      (node (ref "D16") (pin "A") (pinfunction "A_A") (pintype "passive"))
      (node (ref "D19") (pin "A") (pinfunction "A_A") (pintype "passive"))
      (node (ref "U$2") (pin "L2") (pinfunction "1_L2") (pintype "bidirectional"))
    )
    (net (code "55") (name "Net-(U$2K-1)") (class "Default")
      (node (ref "D4") (pin "A") (pinfunction "A_A") (pintype "passive"))
      (node (ref "D5") (pin "A") (pinfunction "A_A") (pintype "passive"))
      (node (ref "U$2") (pin "M2") (pinfunction "1_M2") (pintype "bidirectional"))
    )
    (net (code "56") (name "Net-(U$2M-1)") (class "Default")
      (node (ref "D17") (pin "A") (pinfunction "A_A") (pintype "passive"))
      (node (ref "D20") (pin "A") (pinfunction "A_A") (pintype "passive"))
      (node (ref "U$2") (pin "P2") (pinfunction "1_P2") (pintype "bidirectional"))
    )
    (net (code "57") (name "Net-(U$2N-1)") (class "Default")
      (node (ref "D40") (pin "A") (pinfunction "A_A") (pintype "passive"))
      (node (ref "D43") (pin "A") (pinfunction "A_A") (pintype "passive"))
      (node (ref "U$2") (pin "R2") (pinfunction "1_R2") (pintype "bidirectional"))
    )
    (net (code "58") (name "Net-(U$2O-1)") (class "Default")
      (node (ref "D61") (pin "A") (pinfunction "A_A") (pintype "passive"))
      (node (ref "D63") (pin "A") (pinfunction "A_A") (pintype "passive"))
      (node (ref "U$2") (pin "S2") (pinfunction "1_S2") (pintype "bidirectional"))
    )
  )
)
